# Power.net
KiCad netlist of a schematic drawn in Altium Designer
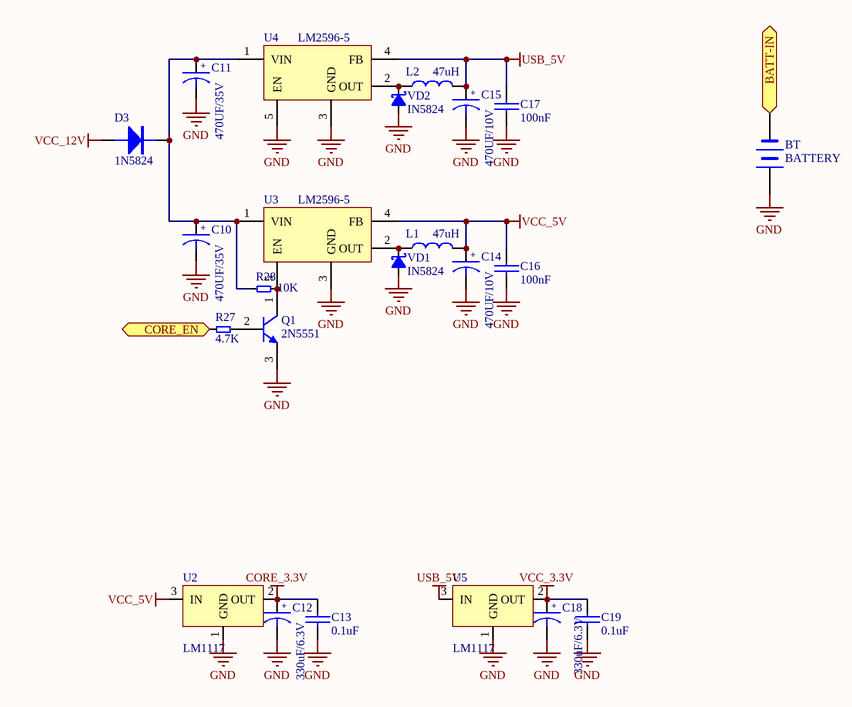
[diagram p0: Power.SchDoc]

(export (version "E")
  (design (tool "Eeschema 10.0.6"))
  (components
    (comp (ref "BT")
      (value "BATTERY")
      (footprint "CR-1220")
      (description "Battery")
      (libsource (lib "标准元件库") (part "BATTERY"))
    )
    (comp (ref "C10")
      (value "470UF/35V")
      (footprint "SMT_10X10_3-AECAP")
      (description "CCTC-106K010")
      (libsource (lib "电容") (part "10UF/10V"))
    )
    (comp (ref "C11")
      (value "470UF/35V")
      (footprint "SMT_10X10_3-AECAP")
      (description "CCTC-106K010")
      (libsource (lib "电容") (part "10UF/10V"))
    )
    (comp (ref "C12")
      (value "330uF/6.3V")
      (footprint "SMT_6_3X7_7-AECAP")
      (description "CCTC-106K010")
      (libsource (lib "电容") (part "10UF/10V"))
    )
    (comp (ref "C13")
      (value "0.1uF")
      (footprint "0805/2012 C3")
      (libsource (lib "*") (part "Pro39.tmp_22P_32"))
    )
    (comp (ref "C14")
      (value "470UF/10V")
      (footprint "SMT_6_3X7_7-AECAP")
      (description "CCTC-106K010")
      (libsource (lib "电容") (part "10UF/10V"))
    )
    (comp (ref "C15")
      (value "470UF/10V")
      (footprint "SMT_6_3X7_7-AECAP")
      (description "CCTC-106K010")
      (libsource (lib "电容") (part "10UF/10V"))
    )
    (comp (ref "C16")
      (value "100nF")
      (footprint "0805/2012 C3")
      (description "104")
      (libsource (lib "*") (part "Pro39.tmp_22P_32"))
    )
    (comp (ref "C17")
      (value "100nF")
      (footprint "0805/2012 C3")
      (description "104")
      (libsource (lib "*") (part "Pro39.tmp_22P_32"))
    )
    (comp (ref "C18")
      (value "330uF/6.3V")
      (footprint "SMT_6_3X7_7-AECAP")
      (description "CCTC-106K010")
      (libsource (lib "电容") (part "10UF/10V"))
    )
    (comp (ref "C19")
      (value "0.1uF")
      (footprint "0805/2012 C3")
      (libsource (lib "*") (part "Pro39.tmp_22P_32"))
    )
    (comp (ref "D3")
      (value "1N5824")
      (footprint "DO-214AC")
      (description "CD-1N5819-DO41")
      (libsource (lib "二极管、整流器件") (part "1N5819"))
    )
    (comp (ref "L1")
      (value "47uH")
      (footprint "MS125")
      (description "12*12电感")
      (libsource (lib "电感、变压器件") (part "100UH-SLF7032"))
    )
    (comp (ref "L2")
      (value "47uH")
      (footprint "MS125")
      (description "12*12电感")
      (libsource (lib "电感、变压器件") (part "100UH-SLF7032"))
    )
    (comp (ref "Q1")
      (value "2N5551")
      (footprint "SOT-23 Q2")
      (description "NPN Bipolar Transistor")
      (fields (field (name "PUBLISHER") "Altium Limited"))
      (libsource (lib "Miscellaneous Devices") (part "NPN"))
    )
    (comp (ref "R27")
      (value "4.7K")
      (footprint "0805/2012 R3")
      (description "Resistor")
      (libsource (lib "标准元件库") (part "RES2"))
    )
    (comp (ref "R28")
      (value "10K")
      (footprint "0805/2012 R3")
      (description "Resistor")
      (libsource (lib "标准元件库") (part "RES2"))
    )
    (comp (ref "U2") (value "LM1117") (footprint "SOT-223") (libsource (lib "电源") (part "LM1117")))
    (comp (ref "U3")
      (value "LM2596-5")
      (footprint "TO-263-5")
      (description "LM2575/2596")
      (libsource (lib "PowerChip") (part "LM2596"))
    )
    (comp (ref "U4")
      (value "LM2596-5")
      (footprint "TO-263-5")
      (description "LM2575/2596")
      (libsource (lib "PowerChip") (part "LM2596"))
    )
    (comp (ref "U5") (value "LM1117") (footprint "SOT-223") (libsource (lib "电源") (part "LM1117")))
    (comp (ref "VD1")
      (value "IN5824")
      (footprint "DO-214AC")
      (description "肖特基")
      (libsource (lib "extend") (part "DIODE SCHOTTKY"))
    )
    (comp (ref "VD2")
      (value "IN5824")
      (footprint "DO-214AC")
      (description "肖特基")
      (libsource (lib "extend") (part "DIODE SCHOTTKY"))
    )
  )
  (nets
    (net (code "1") (name "/BATT-IN") (class "Default")
      (node (ref "BT") (pin "2") (pinfunction "-_2") (pintype "passive"))
    )
    (net (code "2") (name "/CORE_EN") (class "Default")
      (node (ref "R27") (pin "1") (pinfunction "1_1") (pintype "passive"))
    )
    (net (code "3") (name "CORE_3.3V") (class "Default")
      (node (ref "C12") (pin "1") (pinfunction "1_1") (pintype "passive"))
      (node (ref "C13") (pin "1") (pintype "passive"))
      (node (ref "U2") (pin "2") (pinfunction "OUT_2") (pintype "passive"))
      (node (ref "U2") (pin "4") (pintype "passive"))
    )
    (net (code "4") (name "GND") (class "Default")
      (node (ref "BT") (pin "1") (pinfunction "+_1") (pintype "passive"))
      (node (ref "C10") (pin "2") (pinfunction "2_2") (pintype "passive"))
      (node (ref "C11") (pin "2") (pinfunction "2_2") (pintype "passive"))
      (node (ref "C12") (pin "2") (pinfunction "2_2") (pintype "passive"))
      (node (ref "C13") (pin "2") (pintype "passive"))
      (node (ref "C14") (pin "2") (pinfunction "2_2") (pintype "passive"))
      (node (ref "C15") (pin "2") (pinfunction "2_2") (pintype "passive"))
      (node (ref "C16") (pin "2") (pintype "passive"))
      (node (ref "C17") (pin "2") (pintype "passive"))
      (node (ref "C18") (pin "2") (pinfunction "2_2") (pintype "passive"))
      (node (ref "C19") (pin "2") (pintype "passive"))
      (node (ref "Q1") (pin "3") (pinfunction "E_3") (pintype "passive"))
      (node (ref "U2") (pin "1") (pinfunction "GND_1") (pintype "passive"))
      (node (ref "U3") (pin "3") (pinfunction "GND_3") (pintype "power_in"))
      (node (ref "U4") (pin "3") (pinfunction "GND_3") (pintype "power_in"))
      (node (ref "U4") (pin "5") (pinfunction "EN_5") (pintype "passive"))
      (node (ref "U5") (pin "1") (pinfunction "GND_1") (pintype "passive"))
      (node (ref "VD1") (pin "1") (pinfunction "A_1") (pintype "passive"))
      (node (ref "VD2") (pin "1") (pinfunction "A_1") (pintype "passive"))
    )
    (net (code "5") (name "Net-(D3-K)") (class "Default")
      (node (ref "C10") (pin "1") (pinfunction "1_1") (pintype "passive"))
      (node (ref "C11") (pin "1") (pinfunction "1_1") (pintype "passive"))
      (node (ref "D3") (pin "2") (pinfunction "K_2") (pintype "passive"))
      (node (ref "R28") (pin "2") (pinfunction "2_2") (pintype "passive"))
      (node (ref "U3") (pin "1") (pinfunction "VIN_1") (pintype "power_in"))
      (node (ref "U4") (pin "1") (pinfunction "VIN_1") (pintype "power_in"))
    )
    (net (code "6") (name "Net-(Q1-B)") (class "Default")
      (node (ref "Q1") (pin "2") (pinfunction "B_2") (pintype "passive"))
      (node (ref "R27") (pin "2") (pinfunction "2_2") (pintype "passive"))
    )
    (net (code "7") (name "Net-(Q1-C)") (class "Default")
      (node (ref "Q1") (pin "1") (pinfunction "C_1") (pintype "passive"))
      (node (ref "R28") (pin "1") (pinfunction "1_1") (pintype "passive"))
      (node (ref "U3") (pin "5") (pinfunction "EN_5") (pintype "passive"))
    )
    (net (code "8") (name "Net-(U3-OUT)") (class "Default")
      (node (ref "L1") (pin "2") (pinfunction "2_2") (pintype "passive"))
      (node (ref "U3") (pin "2") (pinfunction "OUT_2") (pintype "power_in"))
      (node (ref "VD1") (pin "2") (pinfunction "K_2") (pintype "passive"))
    )
    (net (code "9") (name "Net-(U4-OUT)") (class "Default")
      (node (ref "L2") (pin "2") (pinfunction "2_2") (pintype "passive"))
      (node (ref "U4") (pin "2") (pinfunction "OUT_2") (pintype "power_in"))
      (node (ref "VD2") (pin "2") (pinfunction "K_2") (pintype "passive"))
    )
    (net (code "10") (name "USB_5V") (class "Default")
      (node (ref "C15") (pin "1") (pinfunction "1_1") (pintype "passive"))
      (node (ref "C17") (pin "1") (pintype "passive"))
      (node (ref "L2") (pin "1") (pinfunction "1_1") (pintype "passive"))
      (node (ref "U4") (pin "4") (pinfunction "FB_4") (pintype "passive"))
      (node (ref "U5") (pin "3") (pinfunction "IN_3") (pintype "passive"))
    )
    (net (code "11") (name "VCC_3.3V") (class "Default")
      (node (ref "C18") (pin "1") (pinfunction "1_1") (pintype "passive"))
      (node (ref "C19") (pin "1") (pintype "passive"))
      (node (ref "U5") (pin "2") (pinfunction "OUT_2") (pintype "passive"))
      (node (ref "U5") (pin "4") (pintype "passive"))
    )
    (net (code "12") (name "VCC_5V") (class "Default")
      (node (ref "C14") (pin "1") (pinfunction "1_1") (pintype "passive"))
      (node (ref "C16") (pin "1") (pintype "passive"))
      (node (ref "L1") (pin "1") (pinfunction "1_1") (pintype "passive"))
      (node (ref "U2") (pin "3") (pinfunction "IN_3") (pintype "passive"))
      (node (ref "U3") (pin "4") (pinfunction "FB_4") (pintype "passive"))
    )
    (net (code "13") (name "VCC_12V") (class "Default")
      (node (ref "D3") (pin "1") (pinfunction "A_1") (pintype "passive"))
    )
  )
)
